# prototype_card.net
KiCad netlist of a schematic drawn in EAGLE
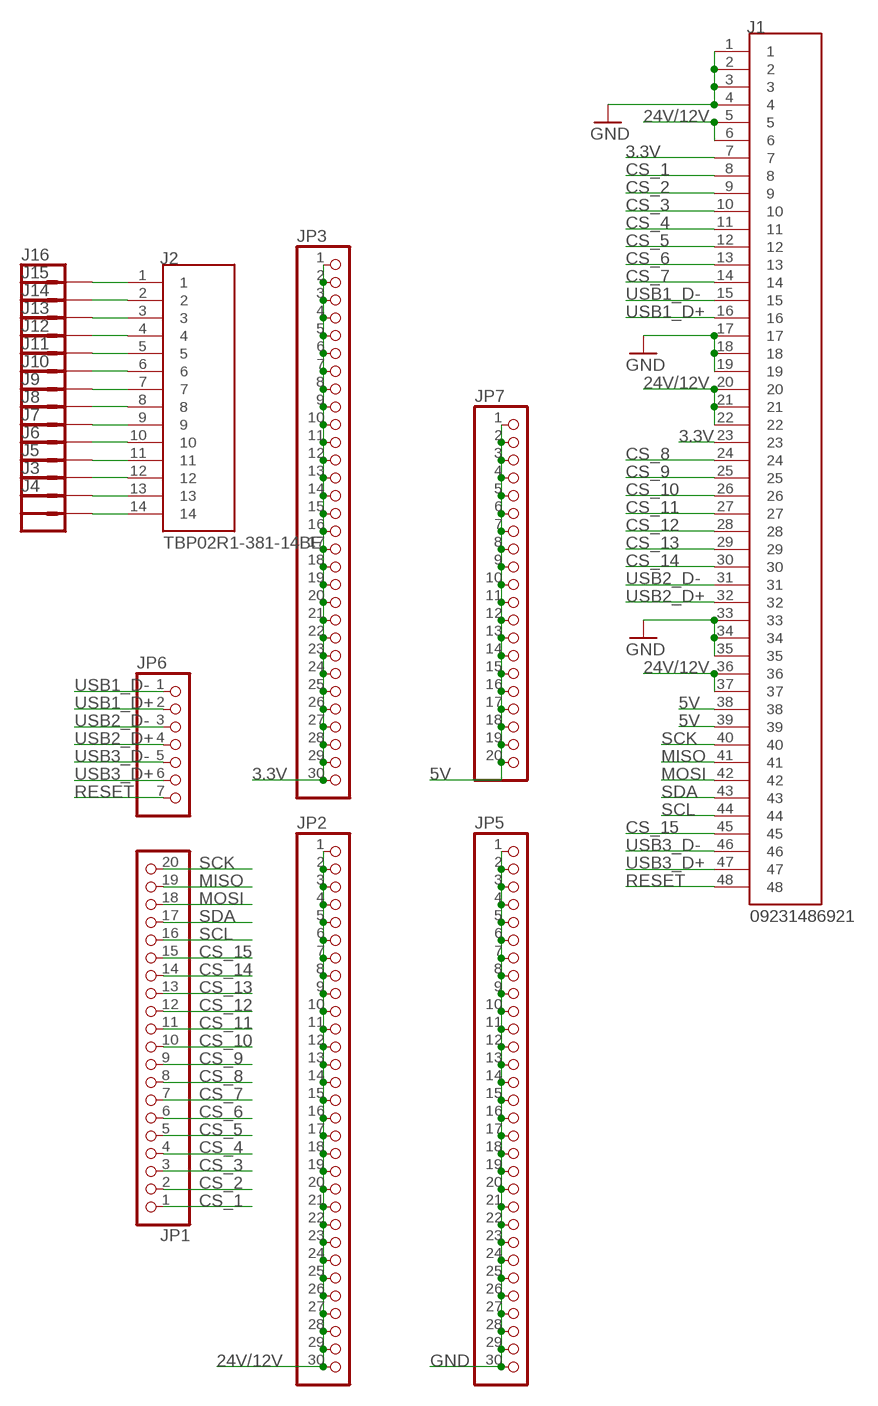
[diagram p0: schematic, sheet 1]

(export (version "E")
  (design (tool "Eeschema 10.0.6"))
  (components
    (comp (ref "J1")
      (value "09231486921")
      (footprint "eagle-import:HARTING_09231486921")
      (fields (field (name "MF") "HARTING"))
      (libsource (lib "eagle-import") (part "09231486921"))
    )
    (comp (ref "J2")
      (value "TBP02R1-381-14BE")
      (footprint "eagle-import:CUI_TBP02R1-381-14BE")
      (fields (field (name "MF") "CUI Devices"))
      (libsource (lib "eagle-import") (part "TBP02R1-381-14BE"))
    )
    (comp (ref "J3")
      (value "CONN_01PTH_LONGPAD")
      (footprint "eagle-import:1X01_LONGPAD")
      (libsource (lib "eagle-import") (part "CONN_01PTH_LONGPAD"))
    )
    (comp (ref "J4")
      (value "CONN_01PTH_LONGPAD")
      (footprint "eagle-import:1X01_LONGPAD")
      (libsource (lib "eagle-import") (part "CONN_01PTH_LONGPAD"))
    )
    (comp (ref "J5")
      (value "CONN_01PTH_LONGPAD")
      (footprint "eagle-import:1X01_LONGPAD")
      (libsource (lib "eagle-import") (part "CONN_01PTH_LONGPAD"))
    )
    (comp (ref "J6")
      (value "CONN_01PTH_LONGPAD")
      (footprint "eagle-import:1X01_LONGPAD")
      (libsource (lib "eagle-import") (part "CONN_01PTH_LONGPAD"))
    )
    (comp (ref "J7")
      (value "CONN_01PTH_LONGPAD")
      (footprint "eagle-import:1X01_LONGPAD")
      (libsource (lib "eagle-import") (part "CONN_01PTH_LONGPAD"))
    )
    (comp (ref "J8")
      (value "CONN_01PTH_LONGPAD")
      (footprint "eagle-import:1X01_LONGPAD")
      (libsource (lib "eagle-import") (part "CONN_01PTH_LONGPAD"))
    )
    (comp (ref "J9")
      (value "CONN_01PTH_LONGPAD")
      (footprint "eagle-import:1X01_LONGPAD")
      (libsource (lib "eagle-import") (part "CONN_01PTH_LONGPAD"))
    )
    (comp (ref "J10")
      (value "CONN_01PTH_LONGPAD")
      (footprint "eagle-import:1X01_LONGPAD")
      (libsource (lib "eagle-import") (part "CONN_01PTH_LONGPAD"))
    )
    (comp (ref "J11")
      (value "CONN_01PTH_LONGPAD")
      (footprint "eagle-import:1X01_LONGPAD")
      (libsource (lib "eagle-import") (part "CONN_01PTH_LONGPAD"))
    )
    (comp (ref "J12")
      (value "CONN_01PTH_LONGPAD")
      (footprint "eagle-import:1X01_LONGPAD")
      (libsource (lib "eagle-import") (part "CONN_01PTH_LONGPAD"))
    )
    (comp (ref "J13")
      (value "CONN_01PTH_LONGPAD")
      (footprint "eagle-import:1X01_LONGPAD")
      (libsource (lib "eagle-import") (part "CONN_01PTH_LONGPAD"))
    )
    (comp (ref "J14")
      (value "CONN_01PTH_LONGPAD")
      (footprint "eagle-import:1X01_LONGPAD")
      (libsource (lib "eagle-import") (part "CONN_01PTH_LONGPAD"))
    )
    (comp (ref "J15")
      (value "CONN_01PTH_LONGPAD")
      (footprint "eagle-import:1X01_LONGPAD")
      (libsource (lib "eagle-import") (part "CONN_01PTH_LONGPAD"))
    )
    (comp (ref "J16")
      (value "CONN_01PTH_LONGPAD")
      (footprint "eagle-import:1X01_LONGPAD")
      (libsource (lib "eagle-import") (part "CONN_01PTH_LONGPAD"))
    )
    (comp (ref "JP1")
      (value "PINHD-1X20")
      (footprint "eagle-import:1X20")
      (libsource (lib "eagle-import") (part "PINHD-1X20"))
    )
    (comp (ref "JP2")
      (value "PINHD-1X30")
      (footprint "eagle-import:1X30")
      (libsource (lib "eagle-import") (part "PINHD-1X30"))
    )
    (comp (ref "JP3")
      (value "PINHD-1X30")
      (footprint "eagle-import:1X30")
      (libsource (lib "eagle-import") (part "PINHD-1X30"))
    )
    (comp (ref "JP5")
      (value "PINHD-1X30")
      (footprint "eagle-import:1X30")
      (libsource (lib "eagle-import") (part "PINHD-1X30"))
    )
    (comp (ref "JP6")
      (value "PINHD-1X7")
      (footprint "eagle-import:1X07")
      (libsource (lib "eagle-import") (part "PINHD-1X7"))
    )
    (comp (ref "JP7")
      (value "PINHD-1X20")
      (footprint "eagle-import:1X20")
      (libsource (lib "eagle-import") (part "PINHD-1X20"))
    )
  )
  (nets
    (net (code "1") (name "/3.3V") (class "Default")
      (node (ref "J1") (pin "23") (pinfunction "23_23") (pintype "passive"))
      (node (ref "J1") (pin "7") (pinfunction "7_7") (pintype "passive"))
      (node (ref "JP3") (pin "1") (pinfunction "1_1") (pintype "passive"))
      (node (ref "JP3") (pin "10") (pinfunction "10_10") (pintype "passive"))
      (node (ref "JP3") (pin "11") (pinfunction "11_11") (pintype "passive"))
      (node (ref "JP3") (pin "12") (pinfunction "12_12") (pintype "passive"))
      (node (ref "JP3") (pin "13") (pinfunction "13_13") (pintype "passive"))
      (node (ref "JP3") (pin "14") (pinfunction "14_14") (pintype "passive"))
      (node (ref "JP3") (pin "15") (pinfunction "15_15") (pintype "passive"))
      (node (ref "JP3") (pin "16") (pinfunction "16_16") (pintype "passive"))
      (node (ref "JP3") (pin "17") (pinfunction "17_17") (pintype "passive"))
      (node (ref "JP3") (pin "18") (pinfunction "18_18") (pintype "passive"))
      (node (ref "JP3") (pin "19") (pinfunction "19_19") (pintype "passive"))
      (node (ref "JP3") (pin "2") (pinfunction "2_2") (pintype "passive"))
      (node (ref "JP3") (pin "20") (pinfunction "20_20") (pintype "passive"))
      (node (ref "JP3") (pin "21") (pinfunction "21_21") (pintype "passive"))
      (node (ref "JP3") (pin "22") (pinfunction "22_22") (pintype "passive"))
      (node (ref "JP3") (pin "23") (pinfunction "23_23") (pintype "passive"))
      (node (ref "JP3") (pin "24") (pinfunction "24_24") (pintype "passive"))
      (node (ref "JP3") (pin "25") (pinfunction "25_25") (pintype "passive"))
      (node (ref "JP3") (pin "26") (pinfunction "26_26") (pintype "passive"))
      (node (ref "JP3") (pin "27") (pinfunction "27_27") (pintype "passive"))
      (node (ref "JP3") (pin "28") (pinfunction "28_28") (pintype "passive"))
      (node (ref "JP3") (pin "29") (pinfunction "29_29") (pintype "passive"))
      (node (ref "JP3") (pin "3") (pinfunction "3_3") (pintype "passive"))
      (node (ref "JP3") (pin "30") (pinfunction "30_30") (pintype "passive"))
      (node (ref "JP3") (pin "4") (pinfunction "4_4") (pintype "passive"))
      (node (ref "JP3") (pin "5") (pinfunction "5_5") (pintype "passive"))
      (node (ref "JP3") (pin "6") (pinfunction "6_6") (pintype "passive"))
      (node (ref "JP3") (pin "7") (pinfunction "7_7") (pintype "passive"))
      (node (ref "JP3") (pin "8") (pinfunction "8_8") (pintype "passive"))
      (node (ref "JP3") (pin "9") (pinfunction "9_9") (pintype "passive"))
    )
    (net (code "2") (name "/5V") (class "Default")
      (node (ref "J1") (pin "38") (pinfunction "38_38") (pintype "passive"))
      (node (ref "J1") (pin "39") (pinfunction "39_39") (pintype "passive"))
      (node (ref "JP7") (pin "1") (pinfunction "1_1") (pintype "passive"))
      (node (ref "JP7") (pin "10") (pinfunction "10_10") (pintype "passive"))
      (node (ref "JP7") (pin "11") (pinfunction "11_11") (pintype "passive"))
      (node (ref "JP7") (pin "12") (pinfunction "12_12") (pintype "passive"))
      (node (ref "JP7") (pin "13") (pinfunction "13_13") (pintype "passive"))
      (node (ref "JP7") (pin "14") (pinfunction "14_14") (pintype "passive"))
      (node (ref "JP7") (pin "15") (pinfunction "15_15") (pintype "passive"))
      (node (ref "JP7") (pin "16") (pinfunction "16_16") (pintype "passive"))
      (node (ref "JP7") (pin "17") (pinfunction "17_17") (pintype "passive"))
      (node (ref "JP7") (pin "18") (pinfunction "18_18") (pintype "passive"))
      (node (ref "JP7") (pin "19") (pinfunction "19_19") (pintype "passive"))
      (node (ref "JP7") (pin "2") (pinfunction "2_2") (pintype "passive"))
      (node (ref "JP7") (pin "20") (pinfunction "20_20") (pintype "passive"))
      (node (ref "JP7") (pin "3") (pinfunction "3_3") (pintype "passive"))
      (node (ref "JP7") (pin "4") (pinfunction "4_4") (pintype "passive"))
      (node (ref "JP7") (pin "5") (pinfunction "5_5") (pintype "passive"))
      (node (ref "JP7") (pin "6") (pinfunction "6_6") (pintype "passive"))
      (node (ref "JP7") (pin "7") (pinfunction "7_7") (pintype "passive"))
      (node (ref "JP7") (pin "8") (pinfunction "8_8") (pintype "passive"))
      (node (ref "JP7") (pin "9") (pinfunction "9_9") (pintype "passive"))
    )
    (net (code "3") (name "/24V{slash}12V") (class "Default")
      (node (ref "J1") (pin "20") (pinfunction "20_20") (pintype "passive"))
      (node (ref "J1") (pin "21") (pinfunction "21_21") (pintype "passive"))
      (node (ref "J1") (pin "22") (pinfunction "22_22") (pintype "passive"))
      (node (ref "J1") (pin "36") (pinfunction "36_36") (pintype "passive"))
      (node (ref "J1") (pin "37") (pinfunction "37_37") (pintype "passive"))
      (node (ref "J1") (pin "5") (pinfunction "5_5") (pintype "passive"))
      (node (ref "J1") (pin "6") (pinfunction "6_6") (pintype "passive"))
      (node (ref "JP2") (pin "1") (pinfunction "1_1") (pintype "passive"))
      (node (ref "JP2") (pin "10") (pinfunction "10_10") (pintype "passive"))
      (node (ref "JP2") (pin "11") (pinfunction "11_11") (pintype "passive"))
      (node (ref "JP2") (pin "12") (pinfunction "12_12") (pintype "passive"))
      (node (ref "JP2") (pin "13") (pinfunction "13_13") (pintype "passive"))
      (node (ref "JP2") (pin "14") (pinfunction "14_14") (pintype "passive"))
      (node (ref "JP2") (pin "15") (pinfunction "15_15") (pintype "passive"))
      (node (ref "JP2") (pin "16") (pinfunction "16_16") (pintype "passive"))
      (node (ref "JP2") (pin "17") (pinfunction "17_17") (pintype "passive"))
      (node (ref "JP2") (pin "18") (pinfunction "18_18") (pintype "passive"))
      (node (ref "JP2") (pin "19") (pinfunction "19_19") (pintype "passive"))
      (node (ref "JP2") (pin "2") (pinfunction "2_2") (pintype "passive"))
      (node (ref "JP2") (pin "20") (pinfunction "20_20") (pintype "passive"))
      (node (ref "JP2") (pin "21") (pinfunction "21_21") (pintype "passive"))
      (node (ref "JP2") (pin "22") (pinfunction "22_22") (pintype "passive"))
      (node (ref "JP2") (pin "23") (pinfunction "23_23") (pintype "passive"))
      (node (ref "JP2") (pin "24") (pinfunction "24_24") (pintype "passive"))
      (node (ref "JP2") (pin "25") (pinfunction "25_25") (pintype "passive"))
      (node (ref "JP2") (pin "26") (pinfunction "26_26") (pintype "passive"))
      (node (ref "JP2") (pin "27") (pinfunction "27_27") (pintype "passive"))
      (node (ref "JP2") (pin "28") (pinfunction "28_28") (pintype "passive"))
      (node (ref "JP2") (pin "29") (pinfunction "29_29") (pintype "passive"))
      (node (ref "JP2") (pin "3") (pinfunction "3_3") (pintype "passive"))
      (node (ref "JP2") (pin "30") (pinfunction "30_30") (pintype "passive"))
      (node (ref "JP2") (pin "4") (pinfunction "4_4") (pintype "passive"))
      (node (ref "JP2") (pin "5") (pinfunction "5_5") (pintype "passive"))
      (node (ref "JP2") (pin "6") (pinfunction "6_6") (pintype "passive"))
      (node (ref "JP2") (pin "7") (pinfunction "7_7") (pintype "passive"))
      (node (ref "JP2") (pin "8") (pinfunction "8_8") (pintype "passive"))
      (node (ref "JP2") (pin "9") (pinfunction "9_9") (pintype "passive"))
    )
    (net (code "4") (name "/CS_1") (class "Default")
      (node (ref "J1") (pin "8") (pinfunction "8_8") (pintype "passive"))
      (node (ref "JP1") (pin "1") (pinfunction "1_1") (pintype "passive"))
    )
    (net (code "5") (name "/CS_2") (class "Default")
      (node (ref "J1") (pin "9") (pinfunction "9_9") (pintype "passive"))
      (node (ref "JP1") (pin "2") (pinfunction "2_2") (pintype "passive"))
    )
    (net (code "6") (name "/CS_3") (class "Default")
      (node (ref "J1") (pin "10") (pinfunction "10_10") (pintype "passive"))
      (node (ref "JP1") (pin "3") (pinfunction "3_3") (pintype "passive"))
    )
    (net (code "7") (name "/CS_4") (class "Default")
      (node (ref "J1") (pin "11") (pinfunction "11_11") (pintype "passive"))
      (node (ref "JP1") (pin "4") (pinfunction "4_4") (pintype "passive"))
    )
    (net (code "8") (name "/CS_5") (class "Default")
      (node (ref "J1") (pin "12") (pinfunction "12_12") (pintype "passive"))
      (node (ref "JP1") (pin "5") (pinfunction "5_5") (pintype "passive"))
    )
    (net (code "9") (name "/CS_6") (class "Default")
      (node (ref "J1") (pin "13") (pinfunction "13_13") (pintype "passive"))
      (node (ref "JP1") (pin "6") (pinfunction "6_6") (pintype "passive"))
    )
    (net (code "10") (name "/CS_7") (class "Default")
      (node (ref "J1") (pin "14") (pinfunction "14_14") (pintype "passive"))
      (node (ref "JP1") (pin "7") (pinfunction "7_7") (pintype "passive"))
    )
    (net (code "11") (name "/CS_8") (class "Default")
      (node (ref "J1") (pin "24") (pinfunction "24_24") (pintype "passive"))
      (node (ref "JP1") (pin "8") (pinfunction "8_8") (pintype "passive"))
    )
    (net (code "12") (name "/CS_9") (class "Default")
      (node (ref "J1") (pin "25") (pinfunction "25_25") (pintype "passive"))
      (node (ref "JP1") (pin "9") (pinfunction "9_9") (pintype "passive"))
    )
    (net (code "13") (name "/CS_10") (class "Default")
      (node (ref "J1") (pin "26") (pinfunction "26_26") (pintype "passive"))
      (node (ref "JP1") (pin "10") (pinfunction "10_10") (pintype "passive"))
    )
    (net (code "14") (name "/CS_11") (class "Default")
      (node (ref "J1") (pin "27") (pinfunction "27_27") (pintype "passive"))
      (node (ref "JP1") (pin "11") (pinfunction "11_11") (pintype "passive"))
    )
    (net (code "15") (name "/CS_12") (class "Default")
      (node (ref "J1") (pin "28") (pinfunction "28_28") (pintype "passive"))
      (node (ref "JP1") (pin "12") (pinfunction "12_12") (pintype "passive"))
    )
    (net (code "16") (name "/CS_13") (class "Default")
      (node (ref "J1") (pin "29") (pinfunction "29_29") (pintype "passive"))
      (node (ref "JP1") (pin "13") (pinfunction "13_13") (pintype "passive"))
    )
    (net (code "17") (name "/CS_14") (class "Default")
      (node (ref "J1") (pin "30") (pinfunction "30_30") (pintype "passive"))
      (node (ref "JP1") (pin "14") (pinfunction "14_14") (pintype "passive"))
    )
    (net (code "18") (name "/CS_15") (class "Default")
      (node (ref "J1") (pin "45") (pinfunction "45_45") (pintype "passive"))
      (node (ref "JP1") (pin "15") (pinfunction "15_15") (pintype "passive"))
    )
    (net (code "19") (name "/MISO") (class "Default")
      (node (ref "J1") (pin "41") (pinfunction "41_41") (pintype "passive"))
      (node (ref "JP1") (pin "19") (pinfunction "19_19") (pintype "passive"))
    )
    (net (code "20") (name "/MOSI") (class "Default")
      (node (ref "J1") (pin "42") (pinfunction "42_42") (pintype "passive"))
      (node (ref "JP1") (pin "18") (pinfunction "18_18") (pintype "passive"))
    )
    (net (code "21") (name "/RESET") (class "Default")
      (node (ref "J1") (pin "48") (pinfunction "48_48") (pintype "passive"))
      (node (ref "JP6") (pin "7") (pinfunction "7_7") (pintype "passive"))
    )
    (net (code "22") (name "/SCK") (class "Default")
      (node (ref "J1") (pin "40") (pinfunction "40_40") (pintype "passive"))
      (node (ref "JP1") (pin "20") (pinfunction "20_20") (pintype "passive"))
    )
    (net (code "23") (name "/SCL") (class "Default")
      (node (ref "J1") (pin "44") (pinfunction "44_44") (pintype "passive"))
      (node (ref "JP1") (pin "16") (pinfunction "16_16") (pintype "passive"))
    )
    (net (code "24") (name "/SDA") (class "Default")
      (node (ref "J1") (pin "43") (pinfunction "43_43") (pintype "passive"))
      (node (ref "JP1") (pin "17") (pinfunction "17_17") (pintype "passive"))
    )
    (net (code "25") (name "/USB1_D+") (class "Default")
      (node (ref "J1") (pin "16") (pinfunction "16_16") (pintype "passive"))
      (node (ref "JP6") (pin "2") (pinfunction "2_2") (pintype "passive"))
    )
    (net (code "26") (name "/USB1_D-") (class "Default")
      (node (ref "J1") (pin "15") (pinfunction "15_15") (pintype "passive"))
      (node (ref "JP6") (pin "1") (pinfunction "1_1") (pintype "passive"))
    )
    (net (code "27") (name "/USB2_D+") (class "Default")
      (node (ref "J1") (pin "32") (pinfunction "32_32") (pintype "passive"))
      (node (ref "JP6") (pin "4") (pinfunction "4_4") (pintype "passive"))
    )
    (net (code "28") (name "/USB2_D-") (class "Default")
      (node (ref "J1") (pin "31") (pinfunction "31_31") (pintype "passive"))
      (node (ref "JP6") (pin "3") (pinfunction "3_3") (pintype "passive"))
    )
    (net (code "29") (name "/USB3_D+") (class "Default")
      (node (ref "J1") (pin "47") (pinfunction "47_47") (pintype "passive"))
      (node (ref "JP6") (pin "6") (pinfunction "6_6") (pintype "passive"))
    )
    (net (code "30") (name "/USB3_D-") (class "Default")
      (node (ref "J1") (pin "46") (pinfunction "46_46") (pintype "passive"))
      (node (ref "JP6") (pin "5") (pinfunction "5_5") (pintype "passive"))
    )
    (net (code "31") (name "GND") (class "Default")
      (node (ref "J1") (pin "1") (pinfunction "1_1") (pintype "passive"))
      (node (ref "J1") (pin "17") (pinfunction "17_17") (pintype "passive"))
      (node (ref "J1") (pin "18") (pinfunction "18_18") (pintype "passive"))
      (node (ref "J1") (pin "19") (pinfunction "19_19") (pintype "passive"))
      (node (ref "J1") (pin "2") (pinfunction "2_2") (pintype "passive"))
      (node (ref "J1") (pin "3") (pinfunction "3_3") (pintype "passive"))
      (node (ref "J1") (pin "33") (pinfunction "33_33") (pintype "passive"))
      (node (ref "J1") (pin "34") (pinfunction "34_34") (pintype "passive"))
      (node (ref "J1") (pin "35") (pinfunction "35_35") (pintype "passive"))
      (node (ref "J1") (pin "4") (pinfunction "4_4") (pintype "passive"))
      (node (ref "JP5") (pin "1") (pinfunction "1_1") (pintype "passive"))
      (node (ref "JP5") (pin "10") (pinfunction "10_10") (pintype "passive"))
      (node (ref "JP5") (pin "11") (pinfunction "11_11") (pintype "passive"))
      (node (ref "JP5") (pin "12") (pinfunction "12_12") (pintype "passive"))
      (node (ref "JP5") (pin "13") (pinfunction "13_13") (pintype "passive"))
      (node (ref "JP5") (pin "14") (pinfunction "14_14") (pintype "passive"))
      (node (ref "JP5") (pin "15") (pinfunction "15_15") (pintype "passive"))
      (node (ref "JP5") (pin "16") (pinfunction "16_16") (pintype "passive"))
      (node (ref "JP5") (pin "17") (pinfunction "17_17") (pintype "passive"))
      (node (ref "JP5") (pin "18") (pinfunction "18_18") (pintype "passive"))
      (node (ref "JP5") (pin "19") (pinfunction "19_19") (pintype "passive"))
      (node (ref "JP5") (pin "2") (pinfunction "2_2") (pintype "passive"))
      (node (ref "JP5") (pin "20") (pinfunction "20_20") (pintype "passive"))
      (node (ref "JP5") (pin "21") (pinfunction "21_21") (pintype "passive"))
      (node (ref "JP5") (pin "22") (pinfunction "22_22") (pintype "passive"))
      (node (ref "JP5") (pin "23") (pinfunction "23_23") (pintype "passive"))
      (node (ref "JP5") (pin "24") (pinfunction "24_24") (pintype "passive"))
      (node (ref "JP5") (pin "25") (pinfunction "25_25") (pintype "passive"))
      (node (ref "JP5") (pin "26") (pinfunction "26_26") (pintype "passive"))
      (node (ref "JP5") (pin "27") (pinfunction "27_27") (pintype "passive"))
      (node (ref "JP5") (pin "28") (pinfunction "28_28") (pintype "passive"))
      (node (ref "JP5") (pin "29") (pinfunction "29_29") (pintype "passive"))
      (node (ref "JP5") (pin "3") (pinfunction "3_3") (pintype "passive"))
      (node (ref "JP5") (pin "30") (pinfunction "30_30") (pintype "passive"))
      (node (ref "JP5") (pin "4") (pinfunction "4_4") (pintype "passive"))
      (node (ref "JP5") (pin "5") (pinfunction "5_5") (pintype "passive"))
      (node (ref "JP5") (pin "6") (pinfunction "6_6") (pintype "passive"))
      (node (ref "JP5") (pin "7") (pinfunction "7_7") (pintype "passive"))
      (node (ref "JP5") (pin "8") (pinfunction "8_8") (pintype "passive"))
      (node (ref "JP5") (pin "9") (pinfunction "9_9") (pintype "passive"))
    )
    (net (code "32") (name "Net-(J2-Pad8)") (class "Default")
      (node (ref "J2") (pin "8") (pinfunction "8_8") (pintype "passive"))
      (node (ref "J9") (pin "1") (pinfunction "1_1") (pintype "passive"))
    )
    (net (code "33") (name "Net-(J2-Pad9)") (class "Default")
      (node (ref "J2") (pin "9") (pinfunction "9_9") (pintype "passive"))
      (node (ref "J8") (pin "1") (pinfunction "1_1") (pintype "passive"))
    )
    (net (code "34") (name "Net-(J2-Pad10)") (class "Default")
      (node (ref "J2") (pin "10") (pinfunction "10_10") (pintype "passive"))
      (node (ref "J7") (pin "1") (pinfunction "1_1") (pintype "passive"))
    )
    (net (code "35") (name "Net-(J2-Pad11)") (class "Default")
      (node (ref "J2") (pin "11") (pinfunction "11_11") (pintype "passive"))
      (node (ref "J6") (pin "1") (pinfunction "1_1") (pintype "passive"))
    )
    (net (code "36") (name "Net-(J2-Pad12)") (class "Default")
      (node (ref "J2") (pin "12") (pinfunction "12_12") (pintype "passive"))
      (node (ref "J5") (pin "1") (pinfunction "1_1") (pintype "passive"))
    )
    (net (code "37") (name "Net-(J2-Pad13)") (class "Default")
      (node (ref "J2") (pin "13") (pinfunction "13_13") (pintype "passive"))
      (node (ref "J3") (pin "1") (pinfunction "1_1") (pintype "passive"))
    )
    (net (code "38") (name "Net-(J2-Pad14)") (class "Default")
      (node (ref "J2") (pin "14") (pinfunction "14_14") (pintype "passive"))
      (node (ref "J4") (pin "1") (pinfunction "1_1") (pintype "passive"))
    )
    (net (code "39") (name "Net-(J10-Pad1)") (class "Default")
      (node (ref "J10") (pin "1") (pinfunction "1_1") (pintype "passive"))
      (node (ref "J2") (pin "7") (pinfunction "7_7") (pintype "passive"))
    )
    (net (code "40") (name "Net-(J11-Pad1)") (class "Default")
      (node (ref "J11") (pin "1") (pinfunction "1_1") (pintype "passive"))
      (node (ref "J2") (pin "6") (pinfunction "6_6") (pintype "passive"))
    )
    (net (code "41") (name "Net-(J12-Pad1)") (class "Default")
      (node (ref "J12") (pin "1") (pinfunction "1_1") (pintype "passive"))
      (node (ref "J2") (pin "5") (pinfunction "5_5") (pintype "passive"))
    )
    (net (code "42") (name "Net-(J13-Pad1)") (class "Default")
      (node (ref "J13") (pin "1") (pinfunction "1_1") (pintype "passive"))
      (node (ref "J2") (pin "4") (pinfunction "4_4") (pintype "passive"))
    )
    (net (code "43") (name "Net-(J14-Pad1)") (class "Default")
      (node (ref "J14") (pin "1") (pinfunction "1_1") (pintype "passive"))
      (node (ref "J2") (pin "3") (pinfunction "3_3") (pintype "passive"))
    )
    (net (code "44") (name "Net-(J15-Pad1)") (class "Default")
      (node (ref "J15") (pin "1") (pinfunction "1_1") (pintype "passive"))
      (node (ref "J2") (pin "2") (pinfunction "2_2") (pintype "passive"))
    )
    (net (code "45") (name "Net-(J16-Pad1)") (class "Default")
      (node (ref "J16") (pin "1") (pinfunction "1_1") (pintype "passive"))
      (node (ref "J2") (pin "1") (pinfunction "1_1") (pintype "passive"))
    )
  )
)
